# Buttons-Sch-Altium.net
KiCad netlist of a schematic drawn in Altium Designer
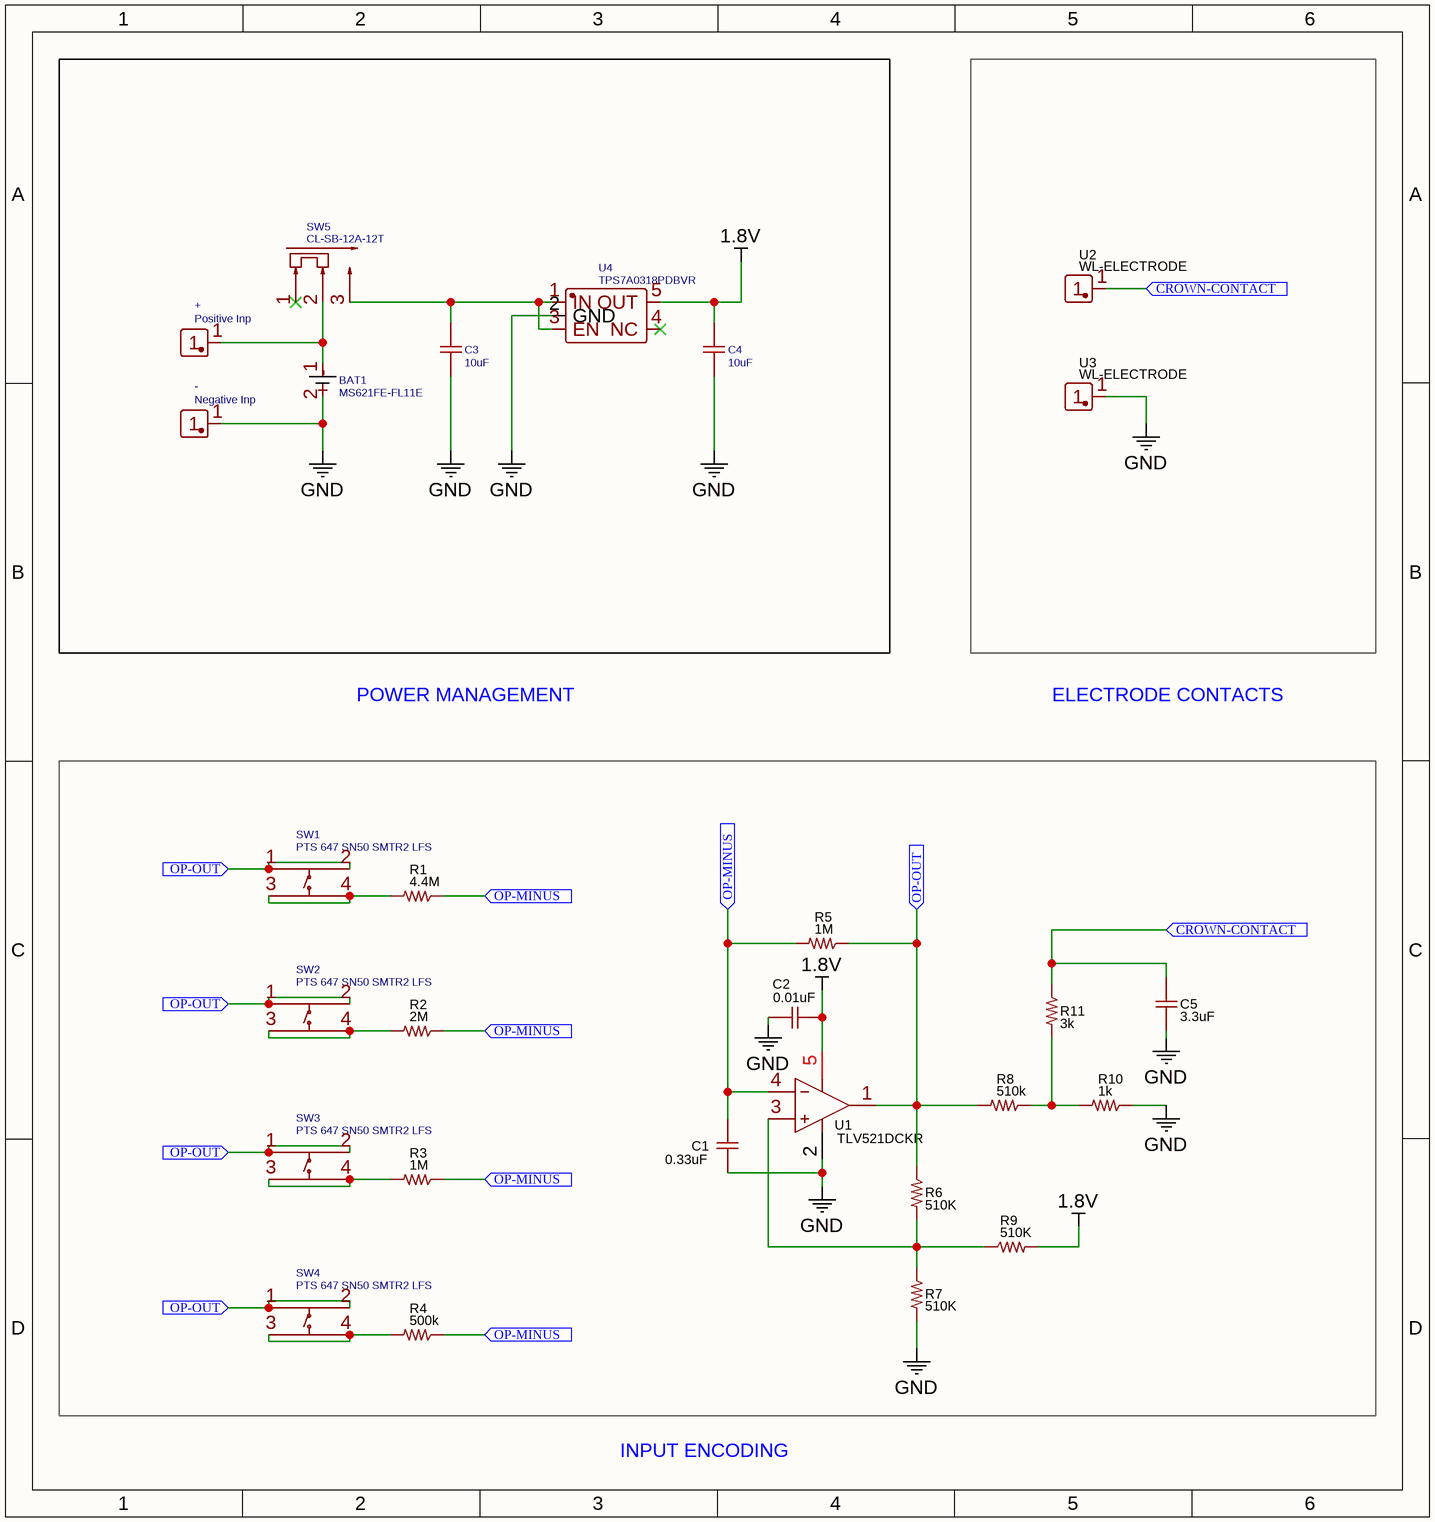
[diagram p0: Buttons-Sch-Altium.schdoc]

(export (version "E")
  (design (tool "Eeschema 10.0.6"))
  (components
    (comp (ref "+")
      (value "Positive Inp")
      (fields (field (name "MANUFACTURER PART") "POGO pin探针") (field (name "CONTRIBUTOR") "rckr"))
      (libsource (lib "altium-import") (part "root_2_Positive Inp_"))
    )
    (comp (ref "-")
      (value "Negative Inp")
      (fields (field (name "MANUFACTURER PART") "POGO pin探针") (field (name "CONTRIBUTOR") "rckr"))
      (libsource (lib "altium-import") (part "root_2_Negative Inp_"))
    )
    (comp (ref "BAT1")
      (value "MS621FE-FL11E")
      (fields
        (field (name "MANUFACTURER") "Panasonic")
        (field (name "MANUFACTURER PART") "ML621 / ML614")
        (field (name "CONTRIBUTOR") "ThijsH")
      )
      (libsource (lib "altium-import") (part "root_0_MS621FE-FL11E_"))
    )
    (comp (ref "C1")
      (value "0.33uF")
      (fields
        (field (name "MANUFACTURER") "YAGEO(国巨)")
        (field (name "MANUFACTURER PART") "CC0402JRX7R8BB473")
        (field (name "CONTRIBUTOR") "rckr")
      )
      (libsource (lib "altium-import") (part "root_3_0.33uF_"))
    )
    (comp (ref "C2")
      (value "0.01uF")
      (fields
        (field (name "MANUFACTURER") "YAGEO(国巨)")
        (field (name "MANUFACTURER PART") "CC0402JRX7R8BB473")
        (field (name "CONTRIBUTOR") "rckr")
      )
      (libsource (lib "altium-import") (part "root_2_0.01uF_"))
    )
    (comp (ref "C3")
      (value "10uF")
      (fields
        (field (name "MANUFACTURER") "YAGEO(国巨)")
        (field (name "MANUFACTURER PART") "CC0402JRX7R8BB473")
        (field (name "CONTRIBUTOR") "rckr")
      )
      (libsource (lib "altium-import") (part "root_3_10uF_"))
    )
    (comp (ref "C4")
      (value "10uF")
      (fields
        (field (name "MANUFACTURER") "YAGEO(国巨)")
        (field (name "MANUFACTURER PART") "CC0402JRX7R8BB473")
        (field (name "CONTRIBUTOR") "rckr")
      )
      (libsource (lib "altium-import") (part "root_3_10uF_"))
    )
    (comp (ref "C5")
      (value "3.3uF")
      (fields
        (field (name "MANUFACTURER") "YAGEO(国巨)")
        (field (name "MANUFACTURER PART") "CC0402JRX7R8BB473")
        (field (name "CONTRIBUTOR") "rckr")
      )
      (libsource (lib "altium-import") (part "root_3_3.3uF_"))
    )
    (comp (ref "R1")
      (value "4.4M")
      (description "RESISTOR, American symbol")
      (fields (field (name "CONTRIBUTOR") "Adafruit"))
      (libsource (lib "altium-import") (part "root_2_4.4M_"))
    )
    (comp (ref "R2")
      (value "2M")
      (description "RESISTOR, American symbol")
      (fields (field (name "CONTRIBUTOR") "Adafruit"))
      (libsource (lib "altium-import") (part "root_2_2M_"))
    )
    (comp (ref "R3")
      (value "1M")
      (description "RESISTOR, American symbol")
      (fields (field (name "CONTRIBUTOR") "Adafruit"))
      (libsource (lib "altium-import") (part "root_2_1M_"))
    )
    (comp (ref "R4")
      (value "500k")
      (description "RESISTOR, American symbol")
      (fields (field (name "CONTRIBUTOR") "Adafruit"))
      (libsource (lib "altium-import") (part "root_2_500k_"))
    )
    (comp (ref "R5")
      (value "1M")
      (description "RESISTOR, American symbol")
      (fields (field (name "CONTRIBUTOR") "Adafruit"))
      (libsource (lib "altium-import") (part "root_2_1M_"))
    )
    (comp (ref "R6")
      (value "510K")
      (description "RESISTOR, American symbol")
      (fields (field (name "CONTRIBUTOR") "Adafruit"))
      (libsource (lib "altium-import") (part "root_3_510K_"))
    )
    (comp (ref "R7")
      (value "510K")
      (description "RESISTOR, American symbol")
      (fields (field (name "CONTRIBUTOR") "Adafruit"))
      (libsource (lib "altium-import") (part "root_3_510K_"))
    )
    (comp (ref "R8")
      (value "510k")
      (description "RESISTOR, American symbol")
      (fields (field (name "CONTRIBUTOR") "Adafruit"))
      (libsource (lib "altium-import") (part "root_2_510k_"))
    )
    (comp (ref "R9")
      (value "510K")
      (description "RESISTOR, American symbol")
      (fields (field (name "CONTRIBUTOR") "Adafruit"))
      (libsource (lib "altium-import") (part "root_0_510K_"))
    )
    (comp (ref "R10")
      (value "1k")
      (description "RESISTOR, American symbol")
      (fields (field (name "CONTRIBUTOR") "Adafruit"))
      (libsource (lib "altium-import") (part "root_2_1k_"))
    )
    (comp (ref "R11")
      (value "3k")
      (description "RESISTOR, American symbol")
      (fields (field (name "CONTRIBUTOR") "Adafruit"))
      (libsource (lib "altium-import") (part "root_3_3k_"))
    )
    (comp (ref "SW1")
      (value "PTS 647 SN50 SMTR2 LFS")
      (fields
        (field (name "MANUFACTURER") "C&K")
        (field (name "MANUFACTURER PART") "PTS647SN50SMTR2LFS")
        (field (name "CONTRIBUTOR") "LCSC")
      )
      (libsource (lib "altium-import") (part "root_0_PTS 647 SN50 SMTR2 LFS_"))
    )
    (comp (ref "SW2")
      (value "PTS 647 SN50 SMTR2 LFS")
      (fields
        (field (name "MANUFACTURER") "C&K")
        (field (name "MANUFACTURER PART") "PTS647SN50SMTR2LFS")
        (field (name "CONTRIBUTOR") "LCSC")
      )
      (libsource (lib "altium-import") (part "root_0_PTS 647 SN50 SMTR2 LFS_"))
    )
    (comp (ref "SW3")
      (value "PTS 647 SN50 SMTR2 LFS")
      (fields
        (field (name "MANUFACTURER") "C&K")
        (field (name "MANUFACTURER PART") "PTS647SN50SMTR2LFS")
        (field (name "CONTRIBUTOR") "LCSC")
      )
      (libsource (lib "altium-import") (part "root_0_PTS 647 SN50 SMTR2 LFS_"))
    )
    (comp (ref "SW4")
      (value "PTS 647 SN50 SMTR2 LFS")
      (fields
        (field (name "MANUFACTURER") "C&K")
        (field (name "MANUFACTURER PART") "PTS647SN50SMTR2LFS")
        (field (name "CONTRIBUTOR") "LCSC")
      )
      (libsource (lib "altium-import") (part "root_0_PTS 647 SN50 SMTR2 LFS_"))
    )
    (comp (ref "SW5")
      (value "CL-SB-12A-12T")
      (fields (field (name "MANUFACTURER") "NIDEC(尼得科)") (field (name "CONTRIBUTOR") "LCSC"))
      (libsource (lib "altium-import") (part "root_0_CL-SB-12A-12T_"))
    )
    (comp (ref "U1")
      (value "TLV521DCKR")
      (fields (field (name "MANUFACTURER") "TI(德州仪器)") (field (name "CONTRIBUTOR") "LCSC"))
      (libsource (lib "altium-import") (part "root_0_TLV521DCKR_"))
    )
    (comp (ref "U2")
      (value "WL-ELECTRODE")
      (fields (field (name "MANUFACTURER PART") "POGO pin探针") (field (name "CONTRIBUTOR") "rckr"))
      (libsource (lib "altium-import") (part "root_2_WL-ELECTRODE_"))
    )
    (comp (ref "U3")
      (value "WL-ELECTRODE")
      (fields (field (name "MANUFACTURER PART") "POGO pin探针") (field (name "CONTRIBUTOR") "rckr"))
      (libsource (lib "altium-import") (part "root_2_WL-ELECTRODE_"))
    )
    (comp (ref "U4")
      (value "TPS7A0318PDBVR")
      (fields (field (name "MANUFACTURER") "TI(德州仪器)") (field (name "CONTRIBUTOR") "lcsc"))
      (libsource (lib "altium-import") (part "root_0_TPS7A0318PDBVR_"))
    )
  )
  (nets
    (net (code "1") (name "/CROWN-CONTACT") (class "Default")
      (node (ref "C5") (pin "1") (pinfunction "1_1") (pintype "passive"))
      (node (ref "R11") (pin "1") (pinfunction "1_1") (pintype "passive"))
      (node (ref "U2") (pin "1") (pinfunction "1_1") (pintype "passive"))
    )
    (net (code "2") (name "/OP-MINUS") (class "Default")
      (node (ref "C1") (pin "1") (pinfunction "1_1") (pintype "passive"))
      (node (ref "R1") (pin "1") (pinfunction "1_1") (pintype "passive"))
      (node (ref "R2") (pin "1") (pinfunction "1_1") (pintype "passive"))
      (node (ref "R3") (pin "1") (pinfunction "1_1") (pintype "passive"))
      (node (ref "R4") (pin "1") (pinfunction "1_1") (pintype "passive"))
      (node (ref "R5") (pin "2") (pinfunction "2_2") (pintype "passive"))
      (node (ref "U1") (pin "4") (pinfunction "IN-_4") (pintype "passive"))
    )
    (net (code "3") (name "/OP-OUT") (class "Default")
      (node (ref "R5") (pin "1") (pinfunction "1_1") (pintype "passive"))
      (node (ref "R6") (pin "1") (pinfunction "1_1") (pintype "passive"))
      (node (ref "R8") (pin "2") (pinfunction "2_2") (pintype "passive"))
      (node (ref "SW1") (pin "1") (pinfunction "1_1") (pintype "passive"))
      (node (ref "SW1") (pin "2") (pinfunction "2_2") (pintype "passive"))
      (node (ref "SW2") (pin "1") (pinfunction "1_1") (pintype "passive"))
      (node (ref "SW2") (pin "2") (pinfunction "2_2") (pintype "passive"))
      (node (ref "SW3") (pin "1") (pinfunction "1_1") (pintype "passive"))
      (node (ref "SW3") (pin "2") (pinfunction "2_2") (pintype "passive"))
      (node (ref "SW4") (pin "1") (pinfunction "1_1") (pintype "passive"))
      (node (ref "SW4") (pin "2") (pinfunction "2_2") (pintype "passive"))
      (node (ref "U1") (pin "1") (pinfunction "OUT_1") (pintype "passive"))
    )
    (net (code "4") (name "1.8V") (class "Default")
      (node (ref "C2") (pin "1") (pinfunction "1_1") (pintype "passive"))
      (node (ref "C4") (pin "1") (pinfunction "1_1") (pintype "passive"))
      (node (ref "R9") (pin "2") (pinfunction "2_2") (pintype "passive"))
      (node (ref "U1") (pin "5") (pinfunction "V+_5") (pintype "passive"))
      (node (ref "U4") (pin "5") (pinfunction "OUT_5") (pintype "passive"))
    )
    (net (code "5") (name "GND") (class "Default")
      (node (ref "-") (pin "1") (pinfunction "1_1") (pintype "passive"))
      (node (ref "BAT1") (pin "2") (pinfunction "-_2") (pintype "passive"))
      (node (ref "C1") (pin "2") (pinfunction "2_2") (pintype "passive"))
      (node (ref "C2") (pin "2") (pinfunction "2_2") (pintype "passive"))
      (node (ref "C3") (pin "2") (pinfunction "2_2") (pintype "passive"))
      (node (ref "C4") (pin "2") (pinfunction "2_2") (pintype "passive"))
      (node (ref "C5") (pin "2") (pinfunction "2_2") (pintype "passive"))
      (node (ref "R10") (pin "1") (pinfunction "1_1") (pintype "passive"))
      (node (ref "R7") (pin "2") (pinfunction "2_2") (pintype "passive"))
      (node (ref "U1") (pin "2") (pinfunction "V-_2") (pintype "passive"))
      (node (ref "U3") (pin "1") (pinfunction "1_1") (pintype "passive"))
      (node (ref "U4") (pin "2") (pinfunction "GND_2") (pintype "passive"))
    )
    (net (code "6") (name "Net-(BAT1-+)") (class "Default")
      (node (ref "+") (pin "1") (pinfunction "1_1") (pintype "passive"))
      (node (ref "BAT1") (pin "1") (pinfunction "+_1") (pintype "passive"))
      (node (ref "SW5") (pin "2") (pinfunction "2_2") (pintype "passive"))
    )
    (net (code "7") (name "Net-(R1-Pad2)") (class "Default")
      (node (ref "R1") (pin "2") (pinfunction "2_2") (pintype "passive"))
      (node (ref "SW1") (pin "3") (pinfunction "3_3") (pintype "passive"))
      (node (ref "SW1") (pin "4") (pinfunction "4_4") (pintype "passive"))
    )
    (net (code "8") (name "Net-(R2-Pad2)") (class "Default")
      (node (ref "R2") (pin "2") (pinfunction "2_2") (pintype "passive"))
      (node (ref "SW2") (pin "3") (pinfunction "3_3") (pintype "passive"))
      (node (ref "SW2") (pin "4") (pinfunction "4_4") (pintype "passive"))
    )
    (net (code "9") (name "Net-(R3-Pad2)") (class "Default")
      (node (ref "R3") (pin "2") (pinfunction "2_2") (pintype "passive"))
      (node (ref "SW3") (pin "3") (pinfunction "3_3") (pintype "passive"))
      (node (ref "SW3") (pin "4") (pinfunction "4_4") (pintype "passive"))
    )
    (net (code "10") (name "Net-(R4-Pad2)") (class "Default")
      (node (ref "R4") (pin "2") (pinfunction "2_2") (pintype "passive"))
      (node (ref "SW4") (pin "3") (pinfunction "3_3") (pintype "passive"))
      (node (ref "SW4") (pin "4") (pinfunction "4_4") (pintype "passive"))
    )
    (net (code "11") (name "Net-(R10-Pad2)") (class "Default")
      (node (ref "R10") (pin "2") (pinfunction "2_2") (pintype "passive"))
      (node (ref "R11") (pin "2") (pinfunction "2_2") (pintype "passive"))
      (node (ref "R8") (pin "1") (pinfunction "1_1") (pintype "passive"))
    )
    (net (code "12") (name "Net-(U1-IN+)") (class "Default")
      (node (ref "R6") (pin "2") (pinfunction "2_2") (pintype "passive"))
      (node (ref "R7") (pin "1") (pinfunction "1_1") (pintype "passive"))
      (node (ref "R9") (pin "1") (pinfunction "1_1") (pintype "passive"))
      (node (ref "U1") (pin "3") (pinfunction "IN+_3") (pintype "passive"))
    )
    (net (code "13") (name "Net-(U4-EN)") (class "Default")
      (node (ref "C3") (pin "1") (pinfunction "1_1") (pintype "passive"))
      (node (ref "SW5") (pin "3") (pinfunction "3_3") (pintype "passive"))
      (node (ref "U4") (pin "1") (pinfunction "IN_1") (pintype "passive"))
      (node (ref "U4") (pin "3") (pinfunction "EN_3") (pintype "passive"))
    )
    (net (code "14") (name "unconnected-(SW5-Pad1)") (class "Default")
      (node (ref "SW5") (pin "1") (pinfunction "1_1") (pintype "passive+no_connect"))
    )
    (net (code "15") (name "unconnected-(U4-NC-Pad4)") (class "Default")
      (node (ref "U4") (pin "4") (pinfunction "NC_4") (pintype "passive+no_connect"))
    )
  )
)
